# CAN.net
KiCad netlist of a schematic drawn in Altium Designer
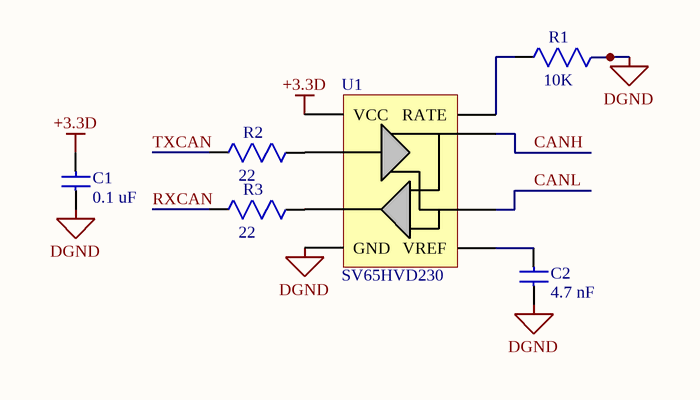
[diagram p0: CAN.SchDoc]

(export (version "E")
  (design (tool "Eeschema 10.0.6"))
  (components
    (comp (ref "C1")
      (value "0.1 uF")
      (footprint "0805")
      (description "CAP CERM 0.1uF")
      (fields
        (field (name "MANUFACTURER") "Yageo")
        (field (name "Comment") "CAP 0.1uF")
        (field (name "SVP CREATOR") "Brett Paulsen")
      )
      (libsource (lib "c3_SchLib") (part "C_0805_0.1uF_1"))
    )
    (comp (ref "C2")
      (value "4.7 nF")
      (footprint "0805")
      (description "CAP CERM 4.7NF")
      (fields (field (name "Comment") "CAP 4.7nF") (field (name "SVP CREATOR") "Jonathan Nutzmann"))
      (libsource (lib "c3_SchLib") (part "C_0805_4.7nF"))
    )
    (comp (ref "R1")
      (value "10K")
      (footprint "0805")
      (description "RES 10K OHM 1/8W 1% 0805 SMD")
      (fields (field (name "Comment") "R_0805_10k_1%") (field (name "SVP CREATOR") "Jonathan Nutzmann"))
      (libsource (lib "c3_SchLib") (part "R_0805_10K_1%"))
    )
    (comp (ref "R2")
      (value "22")
      (footprint "0805")
      (description "RES 22 OHM 1/8W 1% 0805 SMD")
      (fields (field (name "Comment") "R_0805_22_1%") (field (name "SVP CREATOR") "Jonathan Nutzmann"))
      (libsource (lib "c3_SchLib") (part "R_0805_22_1%"))
    )
    (comp (ref "R3")
      (value "22")
      (footprint "0805")
      (description "RES 22 OHM 1/8W 1% 0805 SMD")
      (fields (field (name "Comment") "R_0805_22_1%") (field (name "SVP CREATOR") "Jonathan Nutzmann"))
      (libsource (lib "c3_SchLib") (part "R_0805_22_1%"))
    )
    (comp (ref "U1")
      (value "SV65HVD230")
      (footprint "SOIC127P600-8N")
      (description "CAN Transciever")
      (fields
        (field (name "MANUFACTURER") "Texas Insturments")
        (field (name "Comment") "U_SN65HVD230")
        (field (name "SVP CREATOR") "Jonathan Nutzmann")
      )
      (libsource (lib "c3_SchLib") (part "U_SN65HVD230"))
    )
  )
  (nets
    (net (code "1") (name "+3.3D") (class "Default")
      (node (ref "C1") (pin "1") (pinfunction "1_1") (pintype "passive"))
      (node (ref "U1") (pin "3") (pinfunction "VCC_3") (pintype "power_in"))
    )
    (net (code "2") (name "/CANH") (class "Default")
      (node (ref "U1") (pin "7") (pinfunction "CANH_7") (pintype "passive"))
    )
    (net (code "3") (name "/CANL") (class "Default")
      (node (ref "U1") (pin "6") (pinfunction "CANL_6") (pintype "passive"))
    )
    (net (code "4") (name "/RXCAN") (class "Default")
      (node (ref "R3") (pin "2") (pinfunction "2_2") (pintype "passive"))
    )
    (net (code "5") (name "/TXCAN") (class "Default")
      (node (ref "R2") (pin "2") (pinfunction "2_2") (pintype "passive"))
    )
    (net (code "6") (name "DGND") (class "Default")
      (node (ref "C1") (pin "2") (pinfunction "2_2") (pintype "passive"))
      (node (ref "C2") (pin "2") (pinfunction "2_2") (pintype "passive"))
      (node (ref "R1") (pin "1") (pinfunction "1_1") (pintype "passive"))
      (node (ref "U1") (pin "2") (pinfunction "GND_2") (pintype "power_in"))
    )
    (net (code "7") (name "Net-(U1-RATE)") (class "Default")
      (node (ref "R1") (pin "2") (pinfunction "2_2") (pintype "passive"))
      (node (ref "U1") (pin "8") (pinfunction "RATE_8") (pintype "passive"))
    )
    (net (code "8") (name "Net-(U1-RXD)") (class "Default")
      (node (ref "R3") (pin "1") (pinfunction "1_1") (pintype "passive"))
      (node (ref "U1") (pin "4") (pinfunction "RXD_4") (pintype "passive"))
    )
    (net (code "9") (name "Net-(U1-TXD)") (class "Default")
      (node (ref "R2") (pin "1") (pinfunction "1_1") (pintype "passive"))
      (node (ref "U1") (pin "1") (pinfunction "TXD_1") (pintype "passive"))
    )
    (net (code "10") (name "Net-(U1-VREF)") (class "Default")
      (node (ref "C2") (pin "1") (pinfunction "1_1") (pintype "passive"))
      (node (ref "U1") (pin "5") (pinfunction "VREF_5") (pintype "passive"))
    )
  )
)
